# robotShield_Power.net
KiCad netlist of a schematic drawn in Altium Designer
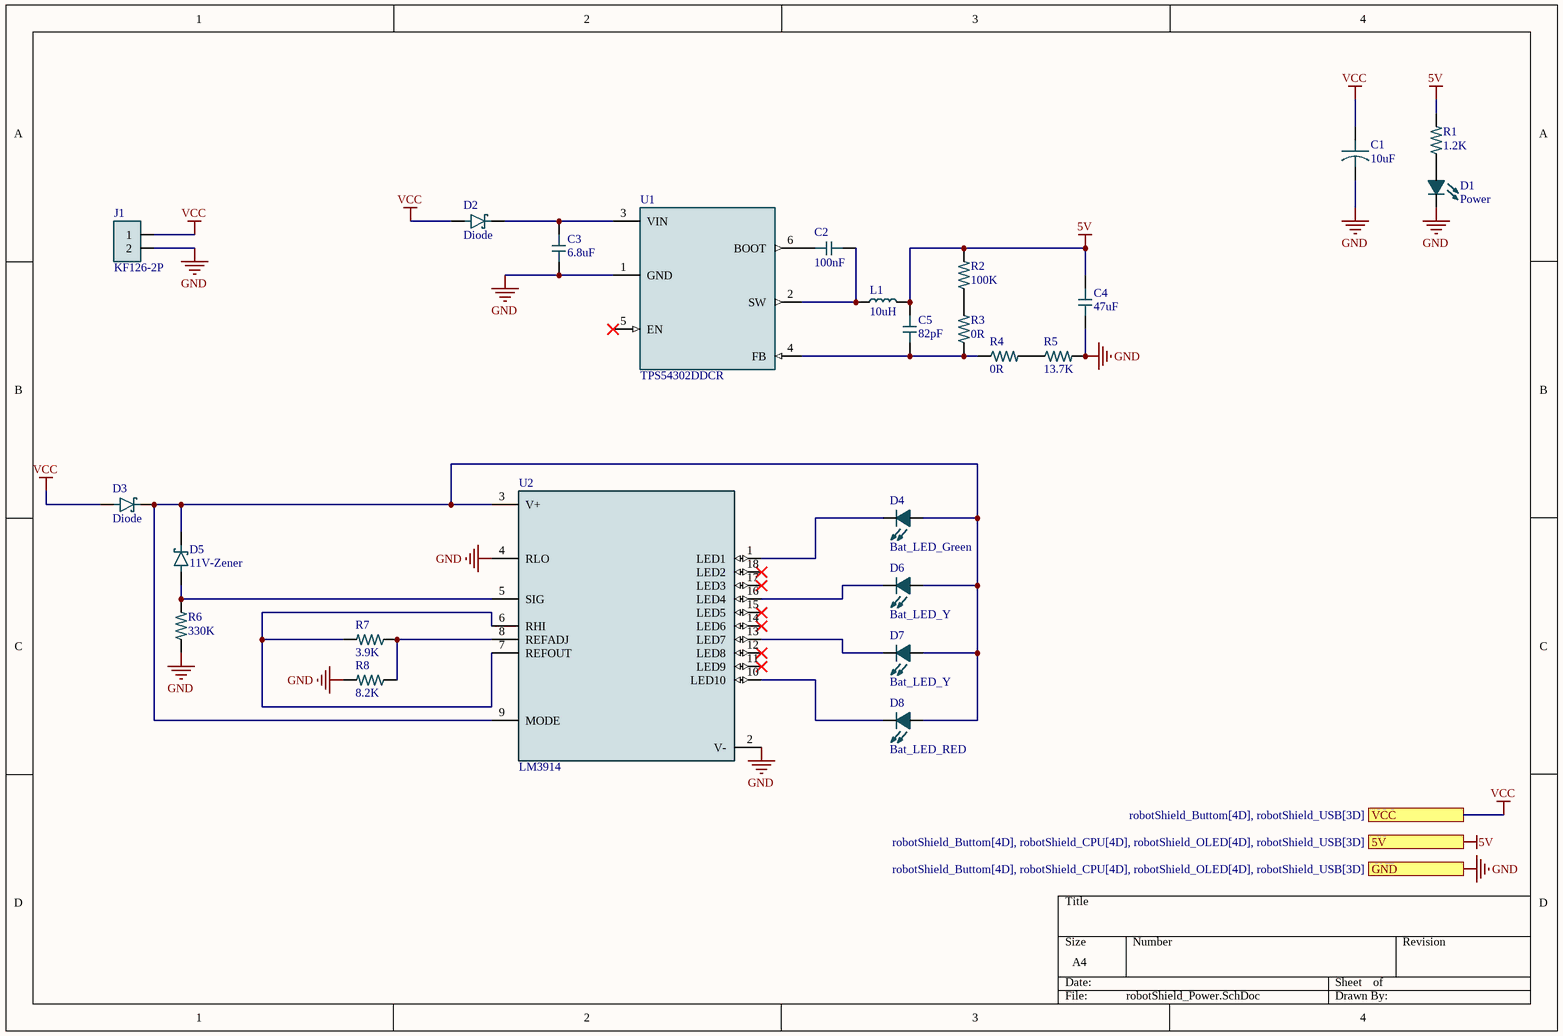
[diagram p0: robotShield_Power.SchDoc]

(export (version "E")
  (design (tool "Eeschema 10.0.6"))
  (components
    (comp (ref "C1")
      (value "10uF")
      (footprint "TAJA")
      (description "Cap Tant Solid SMD 3216-18 3 Ohm 125Â°C T/R")
      (fields (field (name "MF") "AVX") (field (name "MP") "TAJA106K010YNJ"))
      (libsource (lib "Hossein72T") (part "CapacitorP"))
    )
    (comp (ref "C2")
      (value "100nF")
      (footprint "CAP0603")
      (description "CAP SMD")
      (fields (field (name "MF") "AVX") (field (name "MP") "LD031A101GAB2A"))
      (libsource (lib "Hossein72T") (part "Capacitor"))
    )
    (comp (ref "C3")
      (value "6.8uF")
      (footprint "CAP0603")
      (description "CAP SMD")
      (fields (field (name "MF") "AVX") (field (name "MP") "LD031A101GAB2A"))
      (libsource (lib "Hossein72T") (part "Capacitor"))
    )
    (comp (ref "C4")
      (value "47uF")
      (footprint "CAP0603")
      (description "CAP SMD")
      (fields (field (name "MF") "AVX") (field (name "MP") "LD031A101GAB2A"))
      (libsource (lib "Hossein72T") (part "Capacitor"))
    )
    (comp (ref "C5")
      (value "82pF")
      (footprint "CAP0603")
      (description "CAP SMD")
      (fields (field (name "MF") "AVX") (field (name "MP") "LD031A101GAB2A"))
      (libsource (lib "Hossein72T") (part "Capacitor"))
    )
    (comp (ref "D1")
      (value "Power")
      (footprint "LED0603")
      (description "LED")
      (fields (field (name "MP") "LTW-C191TLA"))
      (libsource (lib "Hossein72T") (part "LED"))
    )
    (comp (ref "D2")
      (value "Diode")
      (footprint "SS36")
      (description "Schottky Diode")
      (fields (field (name "MF") "Diotec Semiconductor") (field (name "MP") "S1M"))
      (libsource (lib "Hossein72T") (part "Schottky Diode"))
    )
    (comp (ref "D3")
      (value "Diode")
      (footprint "SS36")
      (description "Schottky Diode")
      (fields (field (name "MF") "Diotec Semiconductor") (field (name "MP") "S1M"))
      (libsource (lib "Hossein72T") (part "Schottky Diode"))
    )
    (comp (ref "D4")
      (value "Bat_LED_Green")
      (footprint "LED0603")
      (description "LED")
      (fields (field (name "MP") "LTW-C191TLA"))
      (libsource (lib "Hossein72T") (part "LED"))
    )
    (comp (ref "D5")
      (value "11V-Zener")
      (footprint "MBR0520LT3G")
      (description "Schottky Diode")
      (fields (field (name "MF") "Diotec Semiconductor") (field (name "MP") "S1M"))
      (libsource (lib "Hossein72T") (part "Schottky Diode"))
    )
    (comp (ref "D6")
      (value "Bat_LED_Y")
      (footprint "LED0603")
      (description "LED")
      (fields (field (name "MP") "LTW-C191TLA"))
      (libsource (lib "Hossein72T") (part "LED"))
    )
    (comp (ref "D7")
      (value "Bat_LED_Y")
      (footprint "LED0603")
      (description "LED")
      (fields (field (name "MP") "LTW-C191TLA"))
      (libsource (lib "Hossein72T") (part "LED"))
    )
    (comp (ref "D8")
      (value "Bat_LED_RED")
      (footprint "LED0603")
      (description "LED")
      (fields (field (name "MP") "LTW-C191TLA"))
      (libsource (lib "Hossein72T") (part "LED"))
    )
    (comp (ref "J1")
      (value "KF126-2P")
      (footprint "KF126-2P")
      (fields (field (name "MF") "TE Connectivity") (field (name "MP") "282836-2"))
      (libsource (lib "Hossein72T") (part "KF126-2P"))
    )
    (comp (ref "L1")
      (value "10uH")
      (footprint "Inductor1515")
      (description "Inductor with Inductance 6.8uH Tol.+/-20%")
      (fields (field (name "MP") "LQM18DN6R8M70B"))
      (libsource (lib "Hossein72T") (part "Inductor"))
    )
    (comp (ref "R1")
      (value "1.2K")
      (footprint "RES0603")
      (description "RES 0.27 OHM 1% 1/10W")
      (fields (field (name "MP") "3-1879460-5") (field (name "MF") "TE Connectivity"))
      (libsource (lib "Hossein72T") (part "Resistor"))
    )
    (comp (ref "R2")
      (value "100K")
      (footprint "RES0603")
      (description "RES 0.27 OHM 1% 1/10W")
      (fields (field (name "MP") "3-1879460-5") (field (name "MF") "TE Connectivity"))
      (libsource (lib "Hossein72T") (part "Resistor"))
    )
    (comp (ref "R3")
      (value "0R")
      (footprint "RES0603")
      (description "RES 0.27 OHM 1% 1/10W")
      (fields (field (name "MP") "3-1879460-5") (field (name "MF") "TE Connectivity"))
      (libsource (lib "Hossein72T") (part "Resistor"))
    )
    (comp (ref "R4")
      (value "0R")
      (footprint "RES0603")
      (description "RES 0.27 OHM 1% 1/10W")
      (fields (field (name "MP") "3-1879460-5") (field (name "MF") "TE Connectivity"))
      (libsource (lib "Hossein72T") (part "Resistor"))
    )
    (comp (ref "R5")
      (value "13.7K")
      (footprint "RES0603")
      (description "RES 0.27 OHM 1% 1/10W")
      (fields (field (name "MP") "3-1879460-5") (field (name "MF") "TE Connectivity"))
      (libsource (lib "Hossein72T") (part "Resistor"))
    )
    (comp (ref "R6")
      (value "330K")
      (footprint "RES0603")
      (description "RES 0.27 OHM 1% 1/10W")
      (fields (field (name "MP") "3-1879460-5") (field (name "MF") "TE Connectivity"))
      (libsource (lib "Hossein72T") (part "Resistor"))
    )
    (comp (ref "R7")
      (value "3.9K")
      (footprint "RES0603")
      (description "RES 0.27 OHM 1% 1/10W")
      (fields (field (name "MP") "3-1879460-5") (field (name "MF") "TE Connectivity"))
      (libsource (lib "Hossein72T") (part "Resistor"))
    )
    (comp (ref "R8")
      (value "8.2K")
      (footprint "RES0603")
      (description "RES 0.27 OHM 1% 1/10W")
      (fields (field (name "MP") "3-1879460-5") (field (name "MF") "TE Connectivity"))
      (libsource (lib "Hossein72T") (part "Resistor"))
    )
    (comp (ref "U1")
      (value "TPS54302DDCR")
      (footprint "TPS54302DDCR")
      (description "4.5-V to 28-V Input, 3-A Output, EMI Friendly Synchronous Step-Down Converter")
      (fields (field (name "MF") "Texas Instruments"))
      (libsource (lib "Hossein72T") (part "TPS54302DDCR"))
    )
    (comp (ref "U2")
      (value "LM3914")
      (footprint "LM3914N-1")
      (description "LED, LCD, Vacuum Fluorescent (VF) Driver 18-PDIP")
      (fields (field (name "MF") "Texas Instruments") (field (name "MP") "LM3914N-1/NOPB"))
      (libsource (lib "Hossein72T") (part "LM3914N-1"))
    )
  )
  (nets
    (net (code "1") (name "5V") (class "Default")
      (node (ref "C4") (pin "1") (pinfunction "1_1") (pintype "passive"))
      (node (ref "C5") (pin "1") (pinfunction "1_1") (pintype "passive"))
      (node (ref "L1") (pin "2") (pinfunction "2_2") (pintype "passive"))
      (node (ref "R1") (pin "2") (pinfunction "2_2") (pintype "passive"))
      (node (ref "R2") (pin "2") (pinfunction "2_2") (pintype "passive"))
    )
    (net (code "2") (name "GND") (class "Default")
      (node (ref "C1") (pin "NEG") (pinfunction "NEG_NEG") (pintype "passive"))
      (node (ref "C3") (pin "2") (pinfunction "2_2") (pintype "passive"))
      (node (ref "C4") (pin "2") (pinfunction "2_2") (pintype "passive"))
      (node (ref "D1") (pin "C") (pinfunction "C_C") (pintype "passive"))
      (node (ref "J1") (pin "2") (pinfunction "2_2") (pintype "passive"))
      (node (ref "R5") (pin "2") (pinfunction "2_2") (pintype "passive"))
      (node (ref "R6") (pin "1") (pinfunction "1_1") (pintype "passive"))
      (node (ref "R8") (pin "2") (pinfunction "2_2") (pintype "passive"))
      (node (ref "U1") (pin "1") (pinfunction "GND_1") (pintype "power_in"))
      (node (ref "U2") (pin "2") (pinfunction "V-_2") (pintype "power_in"))
      (node (ref "U2") (pin "4") (pinfunction "RLO_4") (pintype "power_in"))
    )
    (net (code "3") (name "Net-(D1-PadA)") (class "Default")
      (node (ref "D1") (pin "A") (pinfunction "A_A") (pintype "passive"))
      (node (ref "R1") (pin "1") (pinfunction "1_1") (pintype "passive"))
    )
    (net (code "4") (name "Net-(D2-K)") (class "Default")
      (node (ref "C3") (pin "1") (pinfunction "1_1") (pintype "passive"))
      (node (ref "D2") (pin "C") (pinfunction "K_C") (pintype "passive"))
      (node (ref "U1") (pin "3") (pinfunction "VIN_3") (pintype "power_in"))
    )
    (net (code "5") (name "Net-(D3-K)") (class "Default")
      (node (ref "D3") (pin "C") (pinfunction "K_C") (pintype "passive"))
      (node (ref "D4") (pin "A") (pinfunction "A_A") (pintype "passive"))
      (node (ref "D5") (pin "C") (pinfunction "K_C") (pintype "passive"))
      (node (ref "D6") (pin "A") (pinfunction "A_A") (pintype "passive"))
      (node (ref "D7") (pin "A") (pinfunction "A_A") (pintype "passive"))
      (node (ref "D8") (pin "A") (pinfunction "A_A") (pintype "passive"))
      (node (ref "U2") (pin "3") (pinfunction "V+_3") (pintype "power_in"))
      (node (ref "U2") (pin "9") (pinfunction "MODE_9") (pintype "power_in"))
    )
    (net (code "6") (name "Net-(R2-Pad1)") (class "Default")
      (node (ref "R2") (pin "1") (pinfunction "1_1") (pintype "passive"))
      (node (ref "R3") (pin "2") (pinfunction "2_2") (pintype "passive"))
    )
    (net (code "7") (name "Net-(R4-Pad2)") (class "Default")
      (node (ref "R4") (pin "2") (pinfunction "2_2") (pintype "passive"))
      (node (ref "R5") (pin "1") (pinfunction "1_1") (pintype "passive"))
    )
    (net (code "8") (name "Net-(U1-BOOT)") (class "Default")
      (node (ref "C2") (pin "1") (pinfunction "1_1") (pintype "passive"))
      (node (ref "U1") (pin "6") (pinfunction "BOOT_6") (pintype "output"))
    )
    (net (code "9") (name "Net-(U1-FB)") (class "Default")
      (node (ref "C5") (pin "2") (pinfunction "2_2") (pintype "passive"))
      (node (ref "R3") (pin "1") (pinfunction "1_1") (pintype "passive"))
      (node (ref "R4") (pin "1") (pinfunction "1_1") (pintype "passive"))
      (node (ref "U1") (pin "4") (pinfunction "FB_4") (pintype "input"))
    )
    (net (code "10") (name "Net-(U1-SW)") (class "Default")
      (node (ref "C2") (pin "2") (pinfunction "2_2") (pintype "passive"))
      (node (ref "L1") (pin "1") (pinfunction "1_1") (pintype "passive"))
      (node (ref "U1") (pin "2") (pinfunction "SW_2") (pintype "output"))
    )
    (net (code "11") (name "Net-(U2-LED1)") (class "Default")
      (node (ref "D4") (pin "C") (pinfunction "C_C") (pintype "passive"))
      (node (ref "U2") (pin "1") (pinfunction "LED1_1") (pintype "bidirectional"))
    )
    (net (code "12") (name "Net-(U2-LED4)") (class "Default")
      (node (ref "D6") (pin "C") (pinfunction "C_C") (pintype "passive"))
      (node (ref "U2") (pin "16") (pinfunction "LED4_16") (pintype "bidirectional"))
    )
    (net (code "13") (name "Net-(U2-LED7)") (class "Default")
      (node (ref "D7") (pin "C") (pinfunction "C_C") (pintype "passive"))
      (node (ref "U2") (pin "13") (pinfunction "LED7_13") (pintype "bidirectional"))
    )
    (net (code "14") (name "Net-(U2-LED10)") (class "Default")
      (node (ref "D8") (pin "C") (pinfunction "C_C") (pintype "passive"))
      (node (ref "U2") (pin "10") (pinfunction "LED10_10") (pintype "bidirectional"))
    )
    (net (code "15") (name "Net-(U2-REFADJ)") (class "Default")
      (node (ref "R7") (pin "1") (pinfunction "1_1") (pintype "passive"))
      (node (ref "R8") (pin "1") (pinfunction "1_1") (pintype "passive"))
      (node (ref "U2") (pin "8") (pinfunction "REFADJ_8") (pintype "power_in"))
    )
    (net (code "16") (name "Net-(U2-REFOUT)") (class "Default")
      (node (ref "R7") (pin "2") (pinfunction "2_2") (pintype "passive"))
      (node (ref "U2") (pin "6") (pinfunction "RHI_6") (pintype "power_in"))
      (node (ref "U2") (pin "7") (pinfunction "REFOUT_7") (pintype "power_in"))
    )
    (net (code "17") (name "Net-(U2-SIG)") (class "Default")
      (node (ref "D5") (pin "A") (pinfunction "A_A") (pintype "passive"))
      (node (ref "R6") (pin "2") (pinfunction "2_2") (pintype "passive"))
      (node (ref "U2") (pin "5") (pinfunction "SIG_5") (pintype "power_in"))
    )
    (net (code "18") (name "VCC") (class "Default")
      (node (ref "C1") (pin "POS") (pinfunction "POS_POS") (pintype "passive"))
      (node (ref "D2") (pin "A") (pinfunction "A_A") (pintype "passive"))
      (node (ref "D3") (pin "A") (pinfunction "A_A") (pintype "passive"))
      (node (ref "J1") (pin "1") (pinfunction "1_1") (pintype "passive"))
    )
    (net (code "19") (name "unconnected-(U1-EN-Pad5)") (class "Default")
      (node (ref "U1") (pin "5") (pinfunction "EN_5") (pintype "input+no_connect"))
    )
    (net (code "20") (name "unconnected-(U2-LED2-Pad18)") (class "Default")
      (node (ref "U2") (pin "18") (pinfunction "LED2_18") (pintype "bidirectional+no_connect"))
    )
    (net (code "21") (name "unconnected-(U2-LED3-Pad17)") (class "Default")
      (node (ref "U2") (pin "17") (pinfunction "LED3_17") (pintype "bidirectional+no_connect"))
    )
    (net (code "22") (name "unconnected-(U2-LED5-Pad15)") (class "Default")
      (node (ref "U2") (pin "15") (pinfunction "LED5_15") (pintype "bidirectional+no_connect"))
    )
    (net (code "23") (name "unconnected-(U2-LED6-Pad14)") (class "Default")
      (node (ref "U2") (pin "14") (pinfunction "LED6_14") (pintype "bidirectional+no_connect"))
    )
    (net (code "24") (name "unconnected-(U2-LED8-Pad12)") (class "Default")
      (node (ref "U2") (pin "12") (pinfunction "LED8_12") (pintype "bidirectional+no_connect"))
    )
    (net (code "25") (name "unconnected-(U2-LED9-Pad11)") (class "Default")
      (node (ref "U2") (pin "11") (pinfunction "LED9_11") (pintype "bidirectional+no_connect"))
    )
  )
)
